# Integral_Granite.net
KiCad netlist of a schematic drawn in EAGLE
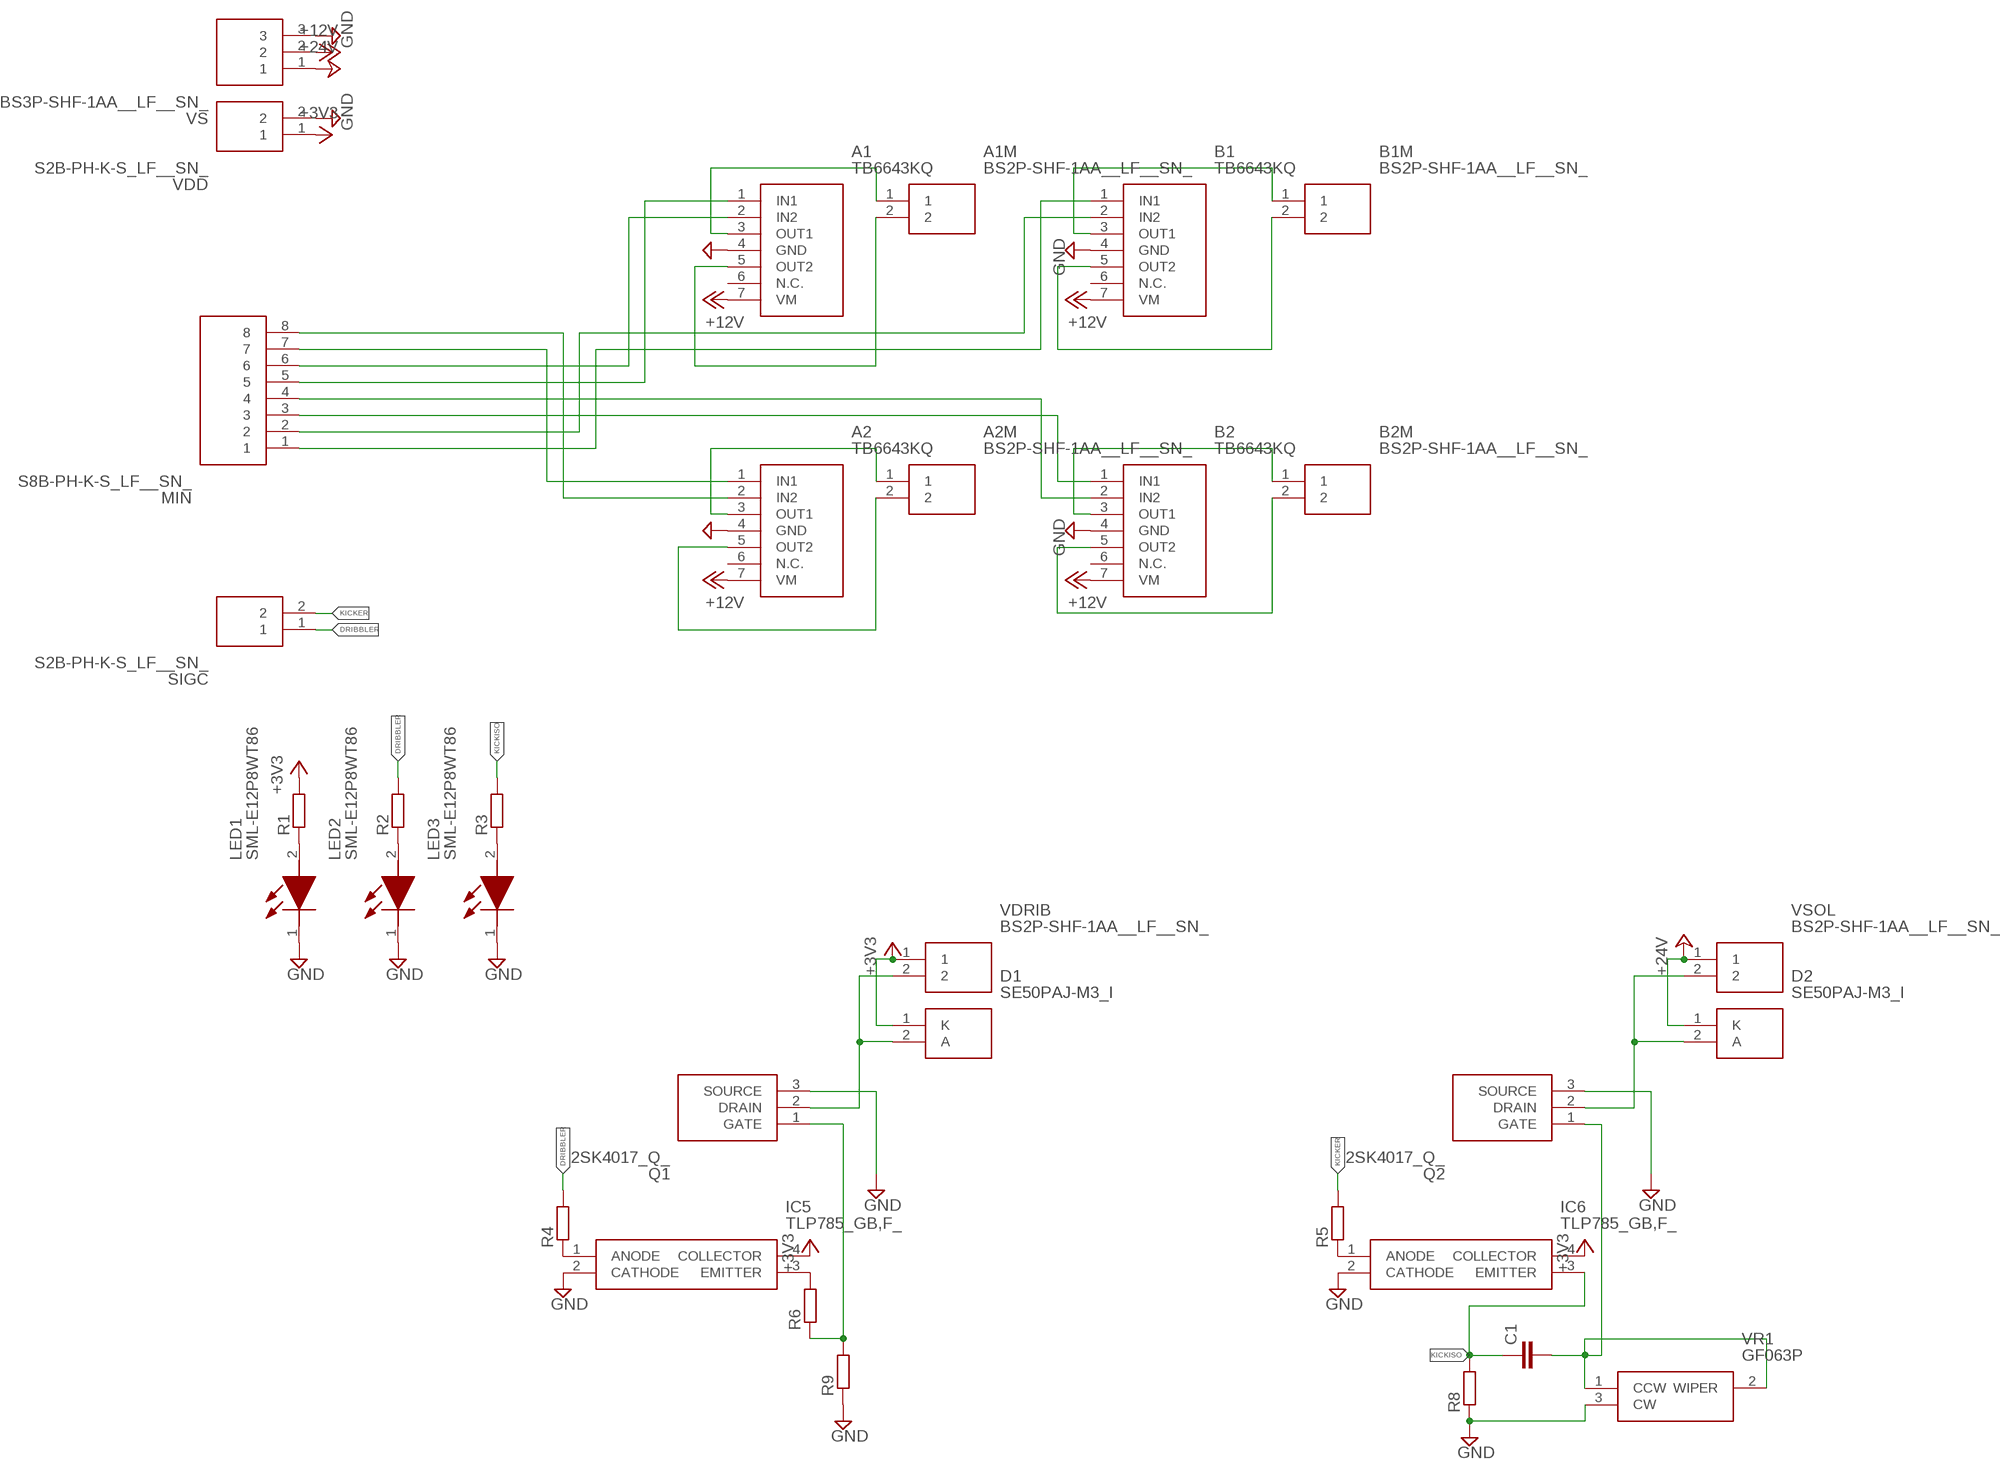
[diagram p0: schematic, sheet 1]

(export (version "E")
  (design (tool "Eeschema 10.0.6"))
  (components
    (comp (ref "A1")
      (value "TB6643KQ")
      (footprint "eagle-import:TB6643KQ")
      (libsource (lib "eagle-import") (part "TB6643KQ"))
    )
    (comp (ref "A1M")
      (value "BS2P-SHF-1AA__LF__SN_")
      (footprint "eagle-import:BS2PSHF1AALFSN")
      (fields
        (field (name "MANUFACTURER_PART_NUMBER") "BS2P-SHF-1AA (LF)(SN)")
        (field (name "RS_PART_NUMBER") "5468552")
      )
      (libsource (lib "eagle-import") (part "BS2P-SHF-1AA__LF__SN_"))
    )
    (comp (ref "A2")
      (value "TB6643KQ")
      (footprint "eagle-import:TB6643KQ")
      (libsource (lib "eagle-import") (part "TB6643KQ"))
    )
    (comp (ref "A2M")
      (value "BS2P-SHF-1AA__LF__SN_")
      (footprint "eagle-import:BS2PSHF1AALFSN")
      (fields
        (field (name "MANUFACTURER_PART_NUMBER") "BS2P-SHF-1AA (LF)(SN)")
        (field (name "RS_PART_NUMBER") "5468552")
      )
      (libsource (lib "eagle-import") (part "BS2P-SHF-1AA__LF__SN_"))
    )
    (comp (ref "B1")
      (value "TB6643KQ")
      (footprint "eagle-import:TB6643KQ")
      (libsource (lib "eagle-import") (part "TB6643KQ"))
    )
    (comp (ref "B1M")
      (value "BS2P-SHF-1AA__LF__SN_")
      (footprint "eagle-import:BS2PSHF1AALFSN")
      (fields
        (field (name "MANUFACTURER_PART_NUMBER") "BS2P-SHF-1AA (LF)(SN)")
        (field (name "RS_PART_NUMBER") "5468552")
      )
      (libsource (lib "eagle-import") (part "BS2P-SHF-1AA__LF__SN_"))
    )
    (comp (ref "B2")
      (value "TB6643KQ")
      (footprint "eagle-import:TB6643KQ")
      (libsource (lib "eagle-import") (part "TB6643KQ"))
    )
    (comp (ref "B2M")
      (value "BS2P-SHF-1AA__LF__SN_")
      (footprint "eagle-import:BS2PSHF1AALFSN")
      (fields
        (field (name "MANUFACTURER_PART_NUMBER") "BS2P-SHF-1AA (LF)(SN)")
        (field (name "RS_PART_NUMBER") "5468552")
      )
      (libsource (lib "eagle-import") (part "BS2P-SHF-1AA__LF__SN_"))
    )
    (comp (ref "C1")
      (value "C-EUC0603")
      (footprint "eagle-import:C0603")
      (libsource (lib "eagle-import") (part "C-EUC0603"))
    )
    (comp (ref "D1")
      (value "SE50PAJ-M3_I")
      (footprint "eagle-import:SE50PAJM3I")
      (fields (field (name "MANUFACTURER_PART_NUMBER") "SE50PAJ-M3/I"))
      (libsource (lib "eagle-import") (part "SE50PAJ-M3_I"))
    )
    (comp (ref "D2")
      (value "SE50PAJ-M3_I")
      (footprint "eagle-import:SE50PAJM3I")
      (fields (field (name "MANUFACTURER_PART_NUMBER") "SE50PAJ-M3/I"))
      (libsource (lib "eagle-import") (part "SE50PAJ-M3_I"))
    )
    (comp (ref "IC5")
      (value "TLP785_GB,F_")
      (footprint "eagle-import:DIP762W60P254L460H425Q4N")
      (fields (field (name "MANUFACTURER_PART_NUMBER") "TLP785(GB,F)"))
      (libsource (lib "eagle-import") (part "TLP785_GB,F_"))
    )
    (comp (ref "IC6")
      (value "TLP785_GB,F_")
      (footprint "eagle-import:DIP762W60P254L460H425Q4N")
      (fields (field (name "MANUFACTURER_PART_NUMBER") "TLP785(GB,F)"))
      (libsource (lib "eagle-import") (part "TLP785_GB,F_"))
    )
    (comp (ref "LED1")
      (value "SML-E12P8WT86")
      (footprint "eagle-import:LEDC1608X36N")
      (fields (field (name "RS_PART_NUMBER") "7526865"))
      (libsource (lib "eagle-import") (part "SML-E12P8WT86"))
    )
    (comp (ref "LED2")
      (value "SML-E12P8WT86")
      (footprint "eagle-import:LEDC1608X36N")
      (fields (field (name "RS_PART_NUMBER") "7526865"))
      (libsource (lib "eagle-import") (part "SML-E12P8WT86"))
    )
    (comp (ref "LED3")
      (value "SML-E12P8WT86")
      (footprint "eagle-import:LEDC1608X36N")
      (fields (field (name "RS_PART_NUMBER") "7526865"))
      (libsource (lib "eagle-import") (part "SML-E12P8WT86"))
    )
    (comp (ref "MIN")
      (value "S8B-PH-K-S_LF__SN_")
      (footprint "eagle-import:SHDRRA8W50P0X200_1X8_1790X760X")
      (fields
        (field (name "MANUFACTURER_PART_NUMBER") "S8B-PH-K-S(LF)(SN)")
        (field (name "RS_PART_NUMBER") "8201517P")
      )
      (libsource (lib "eagle-import") (part "S8B-PH-K-S_LF__SN_"))
    )
    (comp (ref "Q1")
      (value "2SK4017_Q_")
      (footprint "eagle-import:TO230P250X650X900-3P")
      (fields
        (field (name "MANUFACTURER_PART_NUMBER") "2SK4017(Q)")
        (field (name "RS_PART_NUMBER") "0185580")
      )
      (libsource (lib "eagle-import") (part "2SK4017_Q_"))
    )
    (comp (ref "Q2")
      (value "2SK4017_Q_")
      (footprint "eagle-import:TO230P250X650X900-3P")
      (fields
        (field (name "MANUFACTURER_PART_NUMBER") "2SK4017(Q)")
        (field (name "RS_PART_NUMBER") "0185580")
      )
      (libsource (lib "eagle-import") (part "2SK4017_Q_"))
    )
    (comp (ref "R1")
      (value "R-EU_R0603")
      (footprint "eagle-import:R0603")
      (libsource (lib "eagle-import") (part "R-EU_R0603"))
    )
    (comp (ref "R2")
      (value "R-EU_R0603")
      (footprint "eagle-import:R0603")
      (libsource (lib "eagle-import") (part "R-EU_R0603"))
    )
    (comp (ref "R3")
      (value "R-EU_R0603")
      (footprint "eagle-import:R0603")
      (libsource (lib "eagle-import") (part "R-EU_R0603"))
    )
    (comp (ref "R4")
      (value "R-EU_R0603")
      (footprint "eagle-import:R0603")
      (libsource (lib "eagle-import") (part "R-EU_R0603"))
    )
    (comp (ref "R5")
      (value "R-EU_R0603")
      (footprint "eagle-import:R0603")
      (libsource (lib "eagle-import") (part "R-EU_R0603"))
    )
    (comp (ref "R6")
      (value "R-EU_R0603")
      (footprint "eagle-import:R0603")
      (libsource (lib "eagle-import") (part "R-EU_R0603"))
    )
    (comp (ref "R8")
      (value "R-EU_R0603")
      (footprint "eagle-import:R0603")
      (libsource (lib "eagle-import") (part "R-EU_R0603"))
    )
    (comp (ref "R9")
      (value "R-EU_R0603")
      (footprint "eagle-import:R0603")
      (libsource (lib "eagle-import") (part "R-EU_R0603"))
    )
    (comp (ref "SIGC")
      (value "S2B-PH-K-S_LF__SN_")
      (footprint "eagle-import:SHDRRA2W50P0X200_1X2_590X760X4")
      (fields
        (field (name "MANUFACTURER_PART_NUMBER") "S2B-PH-K-S(LF)(SN)")
        (field (name "RS_PART_NUMBER") "8201494P")
      )
      (libsource (lib "eagle-import") (part "S2B-PH-K-S_LF__SN_"))
    )
    (comp (ref "VDD")
      (value "S2B-PH-K-S_LF__SN_")
      (footprint "eagle-import:SHDRRA2W50P0X200_1X2_590X760X4")
      (fields
        (field (name "MANUFACTURER_PART_NUMBER") "S2B-PH-K-S(LF)(SN)")
        (field (name "RS_PART_NUMBER") "8201494P")
      )
      (libsource (lib "eagle-import") (part "S2B-PH-K-S_LF__SN_"))
    )
    (comp (ref "VDRIB")
      (value "BS2P-SHF-1AA__LF__SN_")
      (footprint "eagle-import:BS2PSHF1AALFSN")
      (fields
        (field (name "MANUFACTURER_PART_NUMBER") "BS2P-SHF-1AA (LF)(SN)")
        (field (name "RS_PART_NUMBER") "5468552")
      )
      (libsource (lib "eagle-import") (part "BS2P-SHF-1AA__LF__SN_"))
    )
    (comp (ref "VR1")
      (value "GF063P")
      (footprint "eagle-import:GF063P")
      (libsource (lib "eagle-import") (part "GF063P"))
    )
    (comp (ref "VS")
      (value "BS3P-SHF-1AA__LF__SN_")
      (footprint "eagle-import:HDRRA3W64P0X250_1X3_750X600X56")
      (fields
        (field (name "MANUFACTURER_PART_NUMBER") "BS3P-SHF-1AA (LF)(SN)")
        (field (name "RS_PART_NUMBER") "5468568")
      )
      (libsource (lib "eagle-import") (part "BS3P-SHF-1AA__LF__SN_"))
    )
    (comp (ref "VSOL")
      (value "BS2P-SHF-1AA__LF__SN_")
      (footprint "eagle-import:BS2PSHF1AALFSN")
      (fields
        (field (name "MANUFACTURER_PART_NUMBER") "BS2P-SHF-1AA (LF)(SN)")
        (field (name "RS_PART_NUMBER") "5468552")
      )
      (libsource (lib "eagle-import") (part "BS2P-SHF-1AA__LF__SN_"))
    )
  )
  (nets
    (net (code "1") (name "+3V3") (class "Default")
      (node (ref "D1") (pin "1") (pinfunction "K_1") (pintype "bidirectional"))
      (node (ref "IC5") (pin "4") (pinfunction "COLLECTOR_4") (pintype "bidirectional"))
      (node (ref "IC6") (pin "4") (pinfunction "COLLECTOR_4") (pintype "bidirectional"))
      (node (ref "R1") (pin "2") (pinfunction "2_2") (pintype "passive"))
      (node (ref "VDD") (pin "1") (pinfunction "1_1") (pintype "bidirectional"))
      (node (ref "VDRIB") (pin "1") (pinfunction "1_1") (pintype "bidirectional"))
    )
    (net (code "2") (name "+12V") (class "Default")
      (node (ref "A1") (pin "7") (pinfunction "VM_7") (pintype "bidirectional"))
      (node (ref "A2") (pin "7") (pinfunction "VM_7") (pintype "bidirectional"))
      (node (ref "B1") (pin "7") (pinfunction "VM_7") (pintype "bidirectional"))
      (node (ref "B2") (pin "7") (pinfunction "VM_7") (pintype "bidirectional"))
      (node (ref "VS") (pin "2") (pinfunction "2_2") (pintype "bidirectional"))
    )
    (net (code "3") (name "+24V") (class "Default")
      (node (ref "D2") (pin "1") (pinfunction "K_1") (pintype "bidirectional"))
      (node (ref "VS") (pin "1") (pinfunction "1_1") (pintype "bidirectional"))
      (node (ref "VSOL") (pin "1") (pinfunction "1_1") (pintype "bidirectional"))
    )
    (net (code "4") (name "DRIBBLER") (class "Default")
      (node (ref "R2") (pin "2") (pinfunction "2_2") (pintype "passive"))
      (node (ref "R4") (pin "2") (pinfunction "2_2") (pintype "passive"))
      (node (ref "SIGC") (pin "1") (pinfunction "1_1") (pintype "bidirectional"))
    )
    (net (code "5") (name "GND") (class "Default")
      (node (ref "A1") (pin "4") (pinfunction "GND_4") (pintype "bidirectional"))
      (node (ref "A2") (pin "4") (pinfunction "GND_4") (pintype "bidirectional"))
      (node (ref "B1") (pin "4") (pinfunction "GND_4") (pintype "bidirectional"))
      (node (ref "B2") (pin "4") (pinfunction "GND_4") (pintype "bidirectional"))
      (node (ref "IC5") (pin "2") (pinfunction "CATHODE_2") (pintype "bidirectional"))
      (node (ref "IC6") (pin "2") (pinfunction "CATHODE_2") (pintype "bidirectional"))
      (node (ref "LED1") (pin "1") (pinfunction "K_1") (pintype "bidirectional"))
      (node (ref "LED2") (pin "1") (pinfunction "K_1") (pintype "bidirectional"))
      (node (ref "LED3") (pin "1") (pinfunction "K_1") (pintype "bidirectional"))
      (node (ref "Q1") (pin "3") (pinfunction "SOURCE_3") (pintype "bidirectional"))
      (node (ref "Q2") (pin "3") (pinfunction "SOURCE_3") (pintype "bidirectional"))
      (node (ref "R8") (pin "1") (pinfunction "1_1") (pintype "passive"))
      (node (ref "R9") (pin "1") (pinfunction "1_1") (pintype "passive"))
      (node (ref "VDD") (pin "2") (pinfunction "2_2") (pintype "bidirectional"))
      (node (ref "VR1") (pin "3") (pinfunction "CW_3") (pintype "bidirectional"))
      (node (ref "VS") (pin "3") (pinfunction "3_3") (pintype "bidirectional"))
    )
    (net (code "6") (name "KICKER") (class "Default")
      (node (ref "R5") (pin "2") (pinfunction "2_2") (pintype "passive"))
      (node (ref "SIGC") (pin "2") (pinfunction "2_2") (pintype "bidirectional"))
    )
    (net (code "7") (name "KICKISO") (class "Default")
      (node (ref "C1") (pin "1") (pinfunction "1_1") (pintype "passive"))
      (node (ref "IC6") (pin "3") (pinfunction "EMITTER_3") (pintype "bidirectional"))
      (node (ref "R3") (pin "2") (pinfunction "2_2") (pintype "passive"))
      (node (ref "R8") (pin "2") (pinfunction "2_2") (pintype "passive"))
    )
    (net (code "8") (name "Net-(A1-IN1)") (class "Default")
      (node (ref "A1") (pin "1") (pinfunction "IN1_1") (pintype "bidirectional"))
      (node (ref "MIN") (pin "5") (pinfunction "5_5") (pintype "bidirectional"))
    )
    (net (code "9") (name "Net-(A1-IN2)") (class "Default")
      (node (ref "A1") (pin "2") (pinfunction "IN2_2") (pintype "bidirectional"))
      (node (ref "MIN") (pin "6") (pinfunction "6_6") (pintype "bidirectional"))
    )
    (net (code "10") (name "Net-(A1-OUT1)") (class "Default")
      (node (ref "A1") (pin "3") (pinfunction "OUT1_3") (pintype "bidirectional"))
      (node (ref "A1M") (pin "1") (pinfunction "1_1") (pintype "bidirectional"))
    )
    (net (code "11") (name "Net-(A1-OUT2)") (class "Default")
      (node (ref "A1") (pin "5") (pinfunction "OUT2_5") (pintype "bidirectional"))
      (node (ref "A1M") (pin "2") (pinfunction "2_2") (pintype "bidirectional"))
    )
    (net (code "12") (name "Net-(A2-IN1)") (class "Default")
      (node (ref "A2") (pin "1") (pinfunction "IN1_1") (pintype "bidirectional"))
      (node (ref "MIN") (pin "7") (pinfunction "7_7") (pintype "bidirectional"))
    )
    (net (code "13") (name "Net-(A2-IN2)") (class "Default")
      (node (ref "A2") (pin "2") (pinfunction "IN2_2") (pintype "bidirectional"))
      (node (ref "MIN") (pin "8") (pinfunction "8_8") (pintype "bidirectional"))
    )
    (net (code "14") (name "Net-(A2-OUT1)") (class "Default")
      (node (ref "A2") (pin "3") (pinfunction "OUT1_3") (pintype "bidirectional"))
      (node (ref "A2M") (pin "1") (pinfunction "1_1") (pintype "bidirectional"))
    )
    (net (code "15") (name "Net-(A2-OUT2)") (class "Default")
      (node (ref "A2") (pin "5") (pinfunction "OUT2_5") (pintype "bidirectional"))
      (node (ref "A2M") (pin "2") (pinfunction "2_2") (pintype "bidirectional"))
    )
    (net (code "16") (name "Net-(B1-IN1)") (class "Default")
      (node (ref "B1") (pin "1") (pinfunction "IN1_1") (pintype "bidirectional"))
      (node (ref "MIN") (pin "1") (pinfunction "1_1") (pintype "bidirectional"))
    )
    (net (code "17") (name "Net-(B1-IN2)") (class "Default")
      (node (ref "B1") (pin "2") (pinfunction "IN2_2") (pintype "bidirectional"))
      (node (ref "MIN") (pin "2") (pinfunction "2_2") (pintype "bidirectional"))
    )
    (net (code "18") (name "Net-(B1-OUT1)") (class "Default")
      (node (ref "B1") (pin "3") (pinfunction "OUT1_3") (pintype "bidirectional"))
      (node (ref "B1M") (pin "1") (pinfunction "1_1") (pintype "bidirectional"))
    )
    (net (code "19") (name "Net-(B1-OUT2)") (class "Default")
      (node (ref "B1") (pin "5") (pinfunction "OUT2_5") (pintype "bidirectional"))
      (node (ref "B1M") (pin "2") (pinfunction "2_2") (pintype "bidirectional"))
    )
    (net (code "20") (name "Net-(B2-IN1)") (class "Default")
      (node (ref "B2") (pin "1") (pinfunction "IN1_1") (pintype "bidirectional"))
      (node (ref "MIN") (pin "3") (pinfunction "3_3") (pintype "bidirectional"))
    )
    (net (code "21") (name "Net-(B2-IN2)") (class "Default")
      (node (ref "B2") (pin "2") (pinfunction "IN2_2") (pintype "bidirectional"))
      (node (ref "MIN") (pin "4") (pinfunction "4_4") (pintype "bidirectional"))
    )
    (net (code "22") (name "Net-(B2-OUT1)") (class "Default")
      (node (ref "B2") (pin "3") (pinfunction "OUT1_3") (pintype "bidirectional"))
      (node (ref "B2M") (pin "1") (pinfunction "1_1") (pintype "bidirectional"))
    )
    (net (code "23") (name "Net-(B2-OUT2)") (class "Default")
      (node (ref "B2") (pin "5") (pinfunction "OUT2_5") (pintype "bidirectional"))
      (node (ref "B2M") (pin "2") (pinfunction "2_2") (pintype "bidirectional"))
    )
    (net (code "24") (name "Net-(D1-A)") (class "Default")
      (node (ref "D1") (pin "2") (pinfunction "A_2") (pintype "bidirectional"))
      (node (ref "Q1") (pin "2") (pinfunction "DRAIN_2") (pintype "bidirectional"))
      (node (ref "VDRIB") (pin "2") (pinfunction "2_2") (pintype "bidirectional"))
    )
    (net (code "25") (name "Net-(D2-A)") (class "Default")
      (node (ref "D2") (pin "2") (pinfunction "A_2") (pintype "bidirectional"))
      (node (ref "Q2") (pin "2") (pinfunction "DRAIN_2") (pintype "bidirectional"))
      (node (ref "VSOL") (pin "2") (pinfunction "2_2") (pintype "bidirectional"))
    )
    (net (code "26") (name "Net-(IC5-ANODE)") (class "Default")
      (node (ref "IC5") (pin "1") (pinfunction "ANODE_1") (pintype "bidirectional"))
      (node (ref "R4") (pin "1") (pinfunction "1_1") (pintype "passive"))
    )
    (net (code "27") (name "Net-(IC5-EMITTER)") (class "Default")
      (node (ref "IC5") (pin "3") (pinfunction "EMITTER_3") (pintype "bidirectional"))
      (node (ref "R6") (pin "2") (pinfunction "2_2") (pintype "passive"))
    )
    (net (code "28") (name "Net-(IC6-ANODE)") (class "Default")
      (node (ref "IC6") (pin "1") (pinfunction "ANODE_1") (pintype "bidirectional"))
      (node (ref "R5") (pin "1") (pinfunction "1_1") (pintype "passive"))
    )
    (net (code "29") (name "Net-(LED1-A)") (class "Default")
      (node (ref "LED1") (pin "2") (pinfunction "A_2") (pintype "bidirectional"))
      (node (ref "R1") (pin "1") (pinfunction "1_1") (pintype "passive"))
    )
    (net (code "30") (name "Net-(LED2-A)") (class "Default")
      (node (ref "LED2") (pin "2") (pinfunction "A_2") (pintype "bidirectional"))
      (node (ref "R2") (pin "1") (pinfunction "1_1") (pintype "passive"))
    )
    (net (code "31") (name "Net-(LED3-A)") (class "Default")
      (node (ref "LED3") (pin "2") (pinfunction "A_2") (pintype "bidirectional"))
      (node (ref "R3") (pin "1") (pinfunction "1_1") (pintype "passive"))
    )
    (net (code "32") (name "Net-(Q1-GATE)") (class "Default")
      (node (ref "Q1") (pin "1") (pinfunction "GATE_1") (pintype "bidirectional"))
      (node (ref "R6") (pin "1") (pinfunction "1_1") (pintype "passive"))
      (node (ref "R9") (pin "2") (pinfunction "2_2") (pintype "passive"))
    )
    (net (code "33") (name "Net-(Q2-GATE)") (class "Default")
      (node (ref "C1") (pin "2") (pinfunction "2_2") (pintype "passive"))
      (node (ref "Q2") (pin "1") (pinfunction "GATE_1") (pintype "bidirectional"))
      (node (ref "VR1") (pin "1") (pinfunction "CCW_1") (pintype "bidirectional"))
      (node (ref "VR1") (pin "2") (pinfunction "WIPER_2") (pintype "bidirectional"))
    )
    (net (code "34") (name "unconnected-(A1-N.C.-Pad6)") (class "Default")
      (node (ref "A1") (pin "6") (pinfunction "N.C._6") (pintype "no_connect"))
    )
    (net (code "35") (name "unconnected-(A2-N.C.-Pad6)") (class "Default")
      (node (ref "A2") (pin "6") (pinfunction "N.C._6") (pintype "no_connect"))
    )
    (net (code "36") (name "unconnected-(B1-N.C.-Pad6)") (class "Default")
      (node (ref "B1") (pin "6") (pinfunction "N.C._6") (pintype "no_connect"))
    )
    (net (code "37") (name "unconnected-(B2-N.C.-Pad6)") (class "Default")
      (node (ref "B2") (pin "6") (pinfunction "N.C._6") (pintype "no_connect"))
    )
  )
)
